# encore_Control_Board.net
KiCad netlist of a schematic drawn in EAGLE
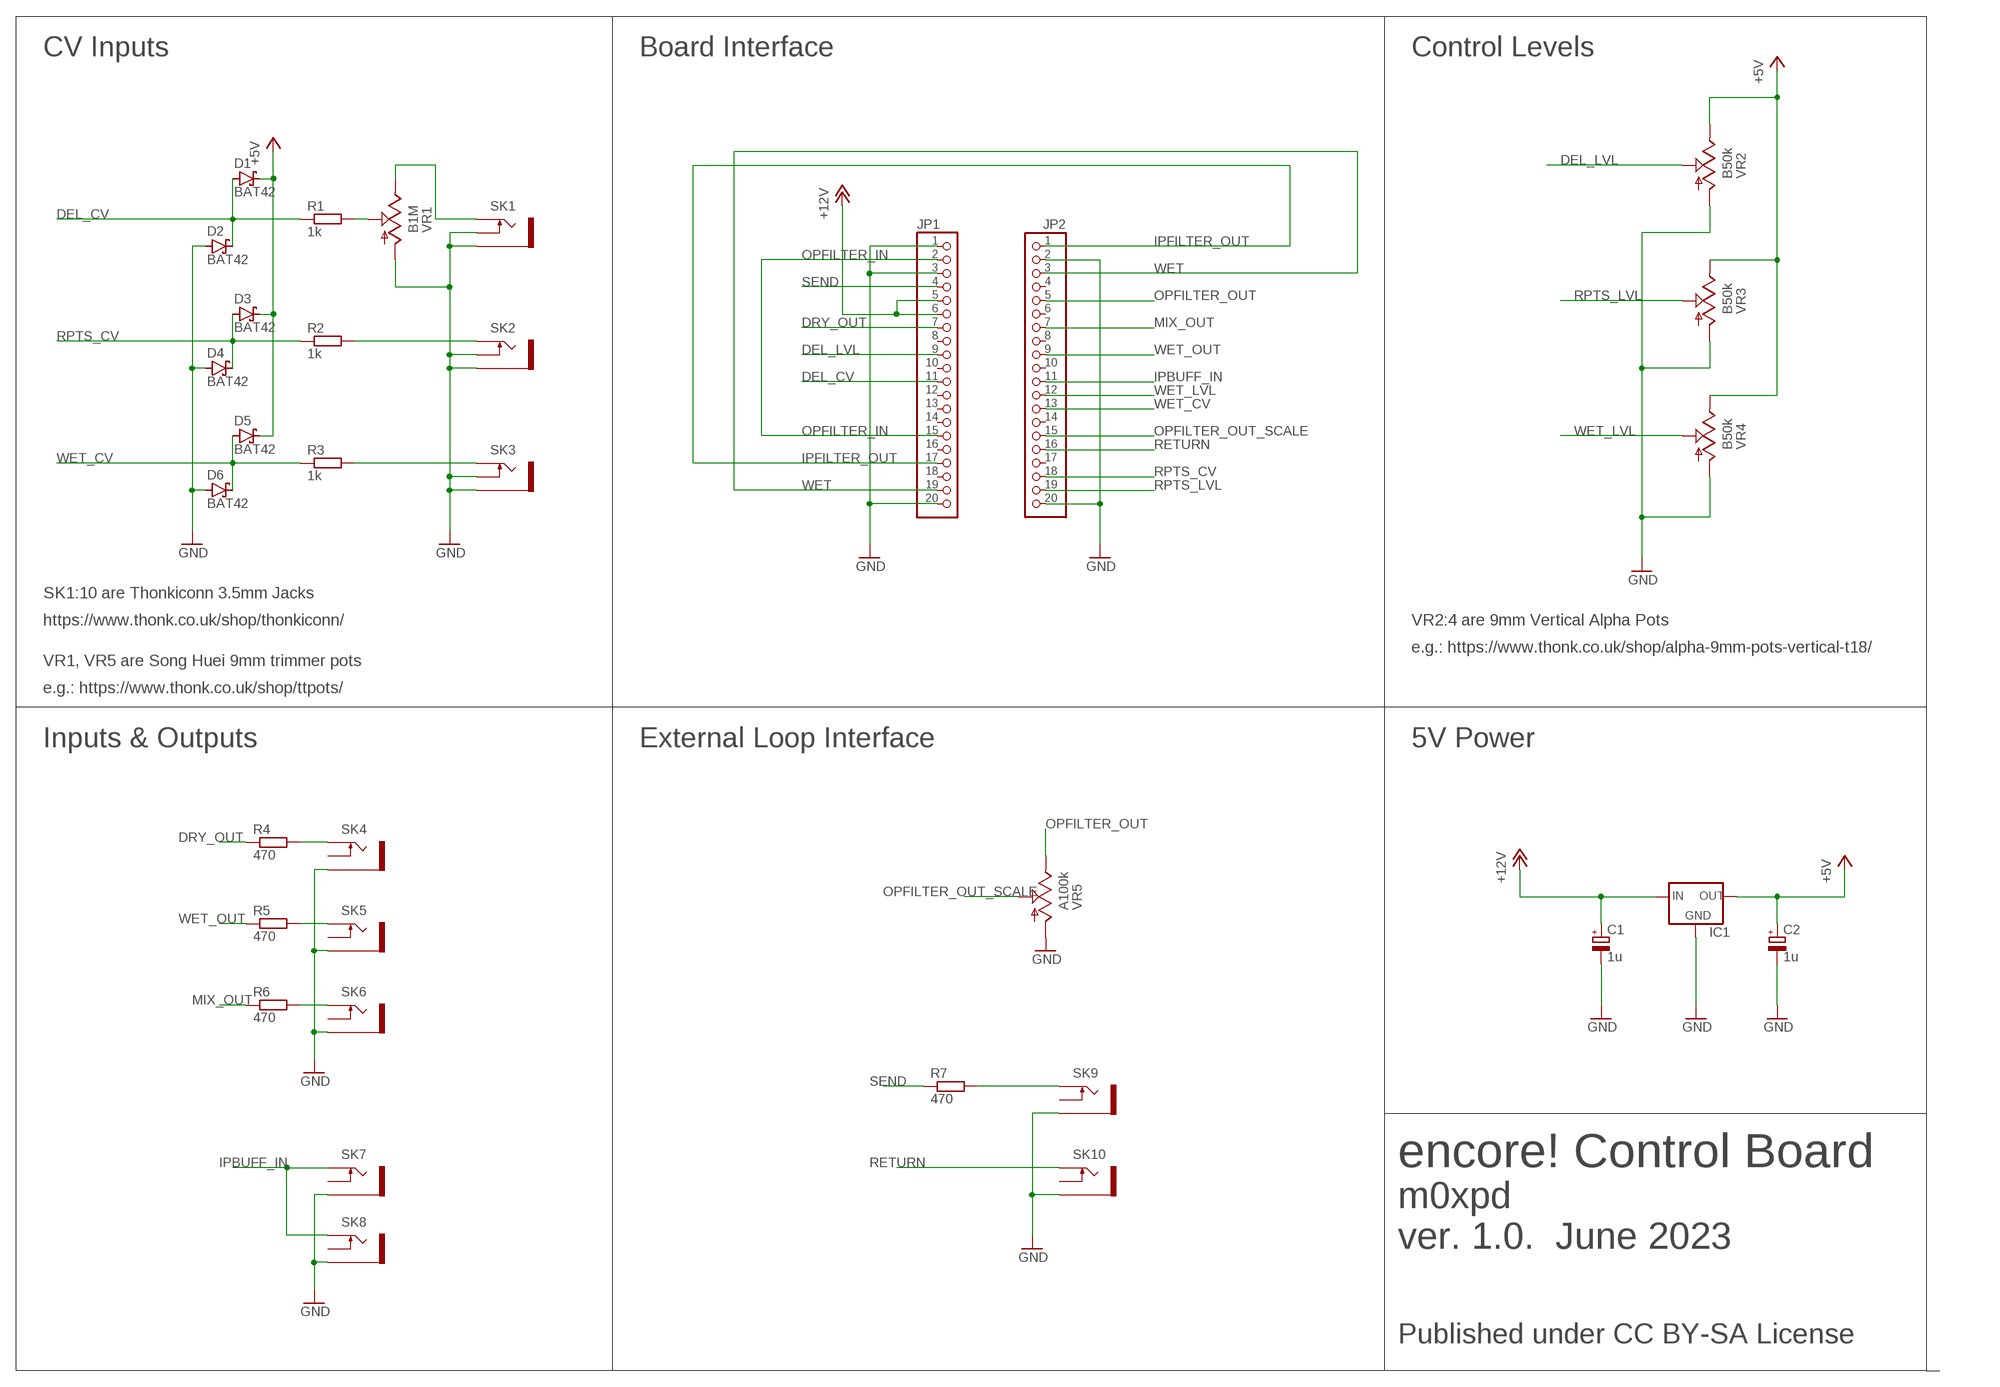
[diagram p0: schematic, sheet 1]

(export (version "E")
  (design (tool "Eeschema 10.0.6"))
  (components
    (comp (ref "C1")
      (value "1u")
      (footprint "eagle-import:E2,5-5")
      (libsource (lib "eagle-import") (part "CPOL-EUE2.5-5"))
    )
    (comp (ref "C2")
      (value "1u")
      (footprint "eagle-import:E2,5-5")
      (libsource (lib "eagle-import") (part "CPOL-EUE2.5-5"))
    )
    (comp (ref "D1")
      (value "BAT42")
      (footprint "eagle-import:DO35-10")
      (libsource (lib "eagle-import") (part "BAT42"))
    )
    (comp (ref "D2")
      (value "BAT42")
      (footprint "eagle-import:DO35-10")
      (libsource (lib "eagle-import") (part "BAT42"))
    )
    (comp (ref "D3")
      (value "BAT42")
      (footprint "eagle-import:DO35-10")
      (libsource (lib "eagle-import") (part "BAT42"))
    )
    (comp (ref "D4")
      (value "BAT42")
      (footprint "eagle-import:DO35-10")
      (libsource (lib "eagle-import") (part "BAT42"))
    )
    (comp (ref "D5")
      (value "BAT42")
      (footprint "eagle-import:DO35-10")
      (libsource (lib "eagle-import") (part "BAT42"))
    )
    (comp (ref "D6")
      (value "BAT42")
      (footprint "eagle-import:DO35-10")
      (libsource (lib "eagle-import") (part "BAT42"))
    )
    (comp (ref "IC1")
      (value "78LXX")
      (footprint "eagle-import:78LXX")
      (libsource (lib "eagle-import") (part "78LXX"))
    )
    (comp (ref "JP1")
      (value "PINHD-1X20")
      (footprint "eagle-import:1X20")
      (libsource (lib "eagle-import") (part "PINHD-1X20"))
    )
    (comp (ref "JP2")
      (value "PINHD-1X20")
      (footprint "eagle-import:1X20")
      (libsource (lib "eagle-import") (part "PINHD-1X20"))
    )
    (comp (ref "R1")
      (value "1k")
      (footprint "eagle-import:0204_7")
      (libsource (lib "eagle-import") (part "R-EU_0204/7"))
    )
    (comp (ref "R2")
      (value "1k")
      (footprint "eagle-import:0204_7")
      (libsource (lib "eagle-import") (part "R-EU_0204/7"))
    )
    (comp (ref "R3")
      (value "1k")
      (footprint "eagle-import:0204_7")
      (libsource (lib "eagle-import") (part "R-EU_0204/7"))
    )
    (comp (ref "R4")
      (value "470")
      (footprint "eagle-import:0204_7")
      (libsource (lib "eagle-import") (part "R-EU_0204/7"))
    )
    (comp (ref "R5")
      (value "470")
      (footprint "eagle-import:0204_7")
      (libsource (lib "eagle-import") (part "R-EU_0204/7"))
    )
    (comp (ref "R6")
      (value "470")
      (footprint "eagle-import:0204_7")
      (libsource (lib "eagle-import") (part "R-EU_0204/7"))
    )
    (comp (ref "R7")
      (value "470")
      (footprint "eagle-import:0204_7")
      (libsource (lib "eagle-import") (part "R-EU_0204/7"))
    )
    (comp (ref "SK1")
      (value "THONKICONN_JACK")
      (footprint "eagle-import:WQP-PJ301M-12_JACK")
      (libsource (lib "eagle-import") (part "THONKICONN_JACK"))
    )
    (comp (ref "SK2")
      (value "THONKICONN_JACK")
      (footprint "eagle-import:WQP-PJ301M-12_JACK")
      (libsource (lib "eagle-import") (part "THONKICONN_JACK"))
    )
    (comp (ref "SK3")
      (value "THONKICONN_JACK")
      (footprint "eagle-import:WQP-PJ301M-12_JACK")
      (libsource (lib "eagle-import") (part "THONKICONN_JACK"))
    )
    (comp (ref "SK4")
      (value "THONKICONN_JACK")
      (footprint "eagle-import:WQP-PJ301M-12_JACK")
      (libsource (lib "eagle-import") (part "THONKICONN_JACK"))
    )
    (comp (ref "SK5")
      (value "THONKICONN_JACK")
      (footprint "eagle-import:WQP-PJ301M-12_JACK")
      (libsource (lib "eagle-import") (part "THONKICONN_JACK"))
    )
    (comp (ref "SK6")
      (value "THONKICONN_JACK")
      (footprint "eagle-import:WQP-PJ301M-12_JACK")
      (libsource (lib "eagle-import") (part "THONKICONN_JACK"))
    )
    (comp (ref "SK7")
      (value "THONKICONN_JACK")
      (footprint "eagle-import:WQP-PJ301M-12_JACK")
      (libsource (lib "eagle-import") (part "THONKICONN_JACK"))
    )
    (comp (ref "SK8")
      (value "THONKICONN_JACK")
      (footprint "eagle-import:WQP-PJ301M-12_JACK")
      (libsource (lib "eagle-import") (part "THONKICONN_JACK"))
    )
    (comp (ref "SK9")
      (value "THONKICONN_JACK")
      (footprint "eagle-import:WQP-PJ301M-12_JACK")
      (libsource (lib "eagle-import") (part "THONKICONN_JACK"))
    )
    (comp (ref "SK10")
      (value "THONKICONN_JACK")
      (footprint "eagle-import:WQP-PJ301M-12_JACK")
      (libsource (lib "eagle-import") (part "THONKICONN_JACK"))
    )
    (comp (ref "VR1")
      (value "B1M")
      (footprint "eagle-import:9MM_SNAP-IN_POT")
      (libsource (lib "eagle-import") (part "9MM_SNAP-IN_POT_"))
    )
    (comp (ref "VR2")
      (value "B50k")
      (footprint "eagle-import:9MM_SNAP-IN_POT")
      (libsource (lib "eagle-import") (part "9MM_SNAP-IN_POT_"))
    )
    (comp (ref "VR3")
      (value "B50k")
      (footprint "eagle-import:9MM_SNAP-IN_POT")
      (libsource (lib "eagle-import") (part "9MM_SNAP-IN_POT_"))
    )
    (comp (ref "VR4")
      (value "B50k")
      (footprint "eagle-import:9MM_SNAP-IN_POT")
      (libsource (lib "eagle-import") (part "9MM_SNAP-IN_POT_"))
    )
    (comp (ref "VR5")
      (value "A100k")
      (footprint "eagle-import:9MM_SNAP-IN_POT")
      (libsource (lib "eagle-import") (part "9MM_SNAP-IN_POT_"))
    )
  )
  (nets
    (net (code "1") (name "+5V") (class "Default")
      (node (ref "C2") (pin "+") (pinfunction "+_+") (pintype "passive"))
      (node (ref "D1") (pin "C") (pinfunction "C_C") (pintype "passive"))
      (node (ref "D3") (pin "C") (pinfunction "C_C") (pintype "passive"))
      (node (ref "D5") (pin "C") (pinfunction "C_C") (pintype "passive"))
      (node (ref "IC1") (pin "OUT") (pinfunction "OUT_OUT") (pintype "passive"))
      (node (ref "VR2") (pin "3") (pinfunction "E_3") (pintype "passive"))
      (node (ref "VR3") (pin "3") (pinfunction "E_3") (pintype "passive"))
      (node (ref "VR4") (pin "3") (pinfunction "E_3") (pintype "passive"))
    )
    (net (code "2") (name "+12V") (class "Default")
      (node (ref "C1") (pin "+") (pinfunction "+_+") (pintype "passive"))
      (node (ref "IC1") (pin "IN") (pinfunction "IN_IN") (pintype "input"))
      (node (ref "JP1") (pin "5") (pinfunction "5_5") (pintype "passive"))
      (node (ref "JP1") (pin "6") (pinfunction "6_6") (pintype "passive"))
    )
    (net (code "3") (name "/DEL_CV") (class "Default")
      (node (ref "D1") (pin "A") (pinfunction "A_A") (pintype "passive"))
      (node (ref "D2") (pin "C") (pinfunction "C_C") (pintype "passive"))
      (node (ref "JP1") (pin "11") (pinfunction "11_11") (pintype "passive"))
      (node (ref "R1") (pin "1") (pinfunction "1_1") (pintype "passive"))
    )
    (net (code "4") (name "/DEL_LVL") (class "Default")
      (node (ref "JP1") (pin "9") (pinfunction "9_9") (pintype "passive"))
      (node (ref "VR2") (pin "2") (pinfunction "S_2") (pintype "passive"))
    )
    (net (code "5") (name "/DRY_OUT") (class "Default")
      (node (ref "JP1") (pin "7") (pinfunction "7_7") (pintype "passive"))
      (node (ref "R4") (pin "1") (pinfunction "1_1") (pintype "passive"))
    )
    (net (code "6") (name "/IPBUFF_IN") (class "Default")
      (node (ref "JP2") (pin "11") (pinfunction "11_11") (pintype "passive"))
      (node (ref "SK7") (pin "P$1_TIP") (pinfunction "TIP_P$1_TIP") (pintype "passive"))
      (node (ref "SK8") (pin "P$1_TIP") (pinfunction "TIP_P$1_TIP") (pintype "passive"))
    )
    (net (code "7") (name "/IPFILTER_OUT") (class "Default")
      (node (ref "JP1") (pin "17") (pinfunction "17_17") (pintype "passive"))
      (node (ref "JP2") (pin "1") (pinfunction "1_1") (pintype "passive"))
    )
    (net (code "8") (name "/MIX_OUT") (class "Default")
      (node (ref "JP2") (pin "7") (pinfunction "7_7") (pintype "passive"))
      (node (ref "R6") (pin "1") (pinfunction "1_1") (pintype "passive"))
    )
    (net (code "9") (name "/OPFILTER_IN") (class "Default")
      (node (ref "JP1") (pin "15") (pinfunction "15_15") (pintype "passive"))
      (node (ref "JP1") (pin "2") (pinfunction "2_2") (pintype "passive"))
    )
    (net (code "10") (name "/OPFILTER_OUT") (class "Default")
      (node (ref "JP2") (pin "5") (pinfunction "5_5") (pintype "passive"))
      (node (ref "VR5") (pin "3") (pinfunction "E_3") (pintype "passive"))
    )
    (net (code "11") (name "/OPFILTER_OUT_SCALE") (class "Default")
      (node (ref "JP2") (pin "15") (pinfunction "15_15") (pintype "passive"))
      (node (ref "VR5") (pin "2") (pinfunction "S_2") (pintype "passive"))
    )
    (net (code "12") (name "/RETURN") (class "Default")
      (node (ref "JP2") (pin "16") (pinfunction "16_16") (pintype "passive"))
      (node (ref "SK10") (pin "P$1_TIP") (pinfunction "TIP_P$1_TIP") (pintype "passive"))
    )
    (net (code "13") (name "/RPTS_CV") (class "Default")
      (node (ref "D3") (pin "A") (pinfunction "A_A") (pintype "passive"))
      (node (ref "D4") (pin "C") (pinfunction "C_C") (pintype "passive"))
      (node (ref "JP2") (pin "18") (pinfunction "18_18") (pintype "passive"))
      (node (ref "R2") (pin "1") (pinfunction "1_1") (pintype "passive"))
    )
    (net (code "14") (name "/RPTS_LVL") (class "Default")
      (node (ref "JP2") (pin "19") (pinfunction "19_19") (pintype "passive"))
      (node (ref "VR3") (pin "2") (pinfunction "S_2") (pintype "passive"))
    )
    (net (code "15") (name "/SEND") (class "Default")
      (node (ref "JP1") (pin "4") (pinfunction "4_4") (pintype "passive"))
      (node (ref "R7") (pin "1") (pinfunction "1_1") (pintype "passive"))
    )
    (net (code "16") (name "/WET") (class "Default")
      (node (ref "JP1") (pin "19") (pinfunction "19_19") (pintype "passive"))
      (node (ref "JP2") (pin "3") (pinfunction "3_3") (pintype "passive"))
    )
    (net (code "17") (name "/WET_CV") (class "Default")
      (node (ref "D5") (pin "A") (pinfunction "A_A") (pintype "passive"))
      (node (ref "D6") (pin "C") (pinfunction "C_C") (pintype "passive"))
      (node (ref "JP2") (pin "13") (pinfunction "13_13") (pintype "passive"))
      (node (ref "R3") (pin "1") (pinfunction "1_1") (pintype "passive"))
    )
    (net (code "18") (name "/WET_LVL") (class "Default")
      (node (ref "JP2") (pin "12") (pinfunction "12_12") (pintype "passive"))
      (node (ref "VR4") (pin "2") (pinfunction "S_2") (pintype "passive"))
    )
    (net (code "19") (name "/WET_OUT") (class "Default")
      (node (ref "JP2") (pin "9") (pinfunction "9_9") (pintype "passive"))
      (node (ref "R5") (pin "1") (pinfunction "1_1") (pintype "passive"))
    )
    (net (code "20") (name "GND") (class "Default")
      (node (ref "C1") (pin "-") (pinfunction "-_-") (pintype "passive"))
      (node (ref "C2") (pin "-") (pinfunction "-_-") (pintype "passive"))
      (node (ref "D2") (pin "A") (pinfunction "A_A") (pintype "passive"))
      (node (ref "D4") (pin "A") (pinfunction "A_A") (pintype "passive"))
      (node (ref "D6") (pin "A") (pinfunction "A_A") (pintype "passive"))
      (node (ref "IC1") (pin "GND") (pinfunction "GND_GND") (pintype "input"))
      (node (ref "JP1") (pin "1") (pinfunction "1_1") (pintype "passive"))
      (node (ref "JP1") (pin "20") (pinfunction "20_20") (pintype "passive"))
      (node (ref "JP1") (pin "3") (pinfunction "3_3") (pintype "passive"))
      (node (ref "JP2") (pin "2") (pinfunction "2_2") (pintype "passive"))
      (node (ref "JP2") (pin "20") (pinfunction "20_20") (pintype "passive"))
      (node (ref "SK1") (pin "P$2_SWITCH") (pinfunction "SWITCH_P$2_SWITCH") (pintype "passive"))
      (node (ref "SK1") (pin "P$3_SLEEVE") (pinfunction "SLEEVE_P$3_SLEEVE") (pintype "passive"))
      (node (ref "SK10") (pin "P$3_SLEEVE") (pinfunction "SLEEVE_P$3_SLEEVE") (pintype "passive"))
      (node (ref "SK2") (pin "P$2_SWITCH") (pinfunction "SWITCH_P$2_SWITCH") (pintype "passive"))
      (node (ref "SK2") (pin "P$3_SLEEVE") (pinfunction "SLEEVE_P$3_SLEEVE") (pintype "passive"))
      (node (ref "SK3") (pin "P$2_SWITCH") (pinfunction "SWITCH_P$2_SWITCH") (pintype "passive"))
      (node (ref "SK3") (pin "P$3_SLEEVE") (pinfunction "SLEEVE_P$3_SLEEVE") (pintype "passive"))
      (node (ref "SK4") (pin "P$3_SLEEVE") (pinfunction "SLEEVE_P$3_SLEEVE") (pintype "passive"))
      (node (ref "SK5") (pin "P$3_SLEEVE") (pinfunction "SLEEVE_P$3_SLEEVE") (pintype "passive"))
      (node (ref "SK6") (pin "P$3_SLEEVE") (pinfunction "SLEEVE_P$3_SLEEVE") (pintype "passive"))
      (node (ref "SK7") (pin "P$3_SLEEVE") (pinfunction "SLEEVE_P$3_SLEEVE") (pintype "passive"))
      (node (ref "SK8") (pin "P$3_SLEEVE") (pinfunction "SLEEVE_P$3_SLEEVE") (pintype "passive"))
      (node (ref "SK9") (pin "P$3_SLEEVE") (pinfunction "SLEEVE_P$3_SLEEVE") (pintype "passive"))
      (node (ref "VR1") (pin "1") (pinfunction "A_1") (pintype "passive"))
      (node (ref "VR2") (pin "1") (pinfunction "A_1") (pintype "passive"))
      (node (ref "VR3") (pin "1") (pinfunction "A_1") (pintype "passive"))
      (node (ref "VR4") (pin "1") (pinfunction "A_1") (pintype "passive"))
      (node (ref "VR5") (pin "1") (pinfunction "A_1") (pintype "passive"))
    )
    (net (code "21") (name "Net-(SK1-TIP)") (class "Default")
      (node (ref "SK1") (pin "P$1_TIP") (pinfunction "TIP_P$1_TIP") (pintype "passive"))
      (node (ref "VR1") (pin "3") (pinfunction "E_3") (pintype "passive"))
    )
    (net (code "22") (name "Net-(SK2-TIP)") (class "Default")
      (node (ref "R2") (pin "2") (pinfunction "2_2") (pintype "passive"))
      (node (ref "SK2") (pin "P$1_TIP") (pinfunction "TIP_P$1_TIP") (pintype "passive"))
    )
    (net (code "23") (name "Net-(SK3-TIP)") (class "Default")
      (node (ref "R3") (pin "2") (pinfunction "2_2") (pintype "passive"))
      (node (ref "SK3") (pin "P$1_TIP") (pinfunction "TIP_P$1_TIP") (pintype "passive"))
    )
    (net (code "24") (name "Net-(SK4-TIP)") (class "Default")
      (node (ref "R4") (pin "2") (pinfunction "2_2") (pintype "passive"))
      (node (ref "SK4") (pin "P$1_TIP") (pinfunction "TIP_P$1_TIP") (pintype "passive"))
    )
    (net (code "25") (name "Net-(SK5-TIP)") (class "Default")
      (node (ref "R5") (pin "2") (pinfunction "2_2") (pintype "passive"))
      (node (ref "SK5") (pin "P$1_TIP") (pinfunction "TIP_P$1_TIP") (pintype "passive"))
    )
    (net (code "26") (name "Net-(SK6-TIP)") (class "Default")
      (node (ref "R6") (pin "2") (pinfunction "2_2") (pintype "passive"))
      (node (ref "SK6") (pin "P$1_TIP") (pinfunction "TIP_P$1_TIP") (pintype "passive"))
    )
    (net (code "27") (name "Net-(SK9-TIP)") (class "Default")
      (node (ref "R7") (pin "2") (pinfunction "2_2") (pintype "passive"))
      (node (ref "SK9") (pin "P$1_TIP") (pinfunction "TIP_P$1_TIP") (pintype "passive"))
    )
    (net (code "28") (name "Net-(VR1-S)") (class "Default")
      (node (ref "R1") (pin "2") (pinfunction "2_2") (pintype "passive"))
      (node (ref "VR1") (pin "2") (pinfunction "S_2") (pintype "passive"))
    )
    (net (code "29") (name "unconnected-(JP1-Pad8)") (class "Default")
      (node (ref "JP1") (pin "8") (pinfunction "8_8") (pintype "passive"))
    )
    (net (code "30") (name "unconnected-(JP1-Pad10)") (class "Default")
      (node (ref "JP1") (pin "10") (pinfunction "10_10") (pintype "passive"))
    )
    (net (code "31") (name "unconnected-(JP1-Pad12)") (class "Default")
      (node (ref "JP1") (pin "12") (pinfunction "12_12") (pintype "passive"))
    )
    (net (code "32") (name "unconnected-(JP1-Pad13)") (class "Default")
      (node (ref "JP1") (pin "13") (pinfunction "13_13") (pintype "passive"))
    )
    (net (code "33") (name "unconnected-(JP1-Pad14)") (class "Default")
      (node (ref "JP1") (pin "14") (pinfunction "14_14") (pintype "passive"))
    )
    (net (code "34") (name "unconnected-(JP1-Pad16)") (class "Default")
      (node (ref "JP1") (pin "16") (pinfunction "16_16") (pintype "passive"))
    )
    (net (code "35") (name "unconnected-(JP1-Pad18)") (class "Default")
      (node (ref "JP1") (pin "18") (pinfunction "18_18") (pintype "passive"))
    )
    (net (code "36") (name "unconnected-(JP2-Pad4)") (class "Default")
      (node (ref "JP2") (pin "4") (pinfunction "4_4") (pintype "passive"))
    )
    (net (code "37") (name "unconnected-(JP2-Pad6)") (class "Default")
      (node (ref "JP2") (pin "6") (pinfunction "6_6") (pintype "passive"))
    )
    (net (code "38") (name "unconnected-(JP2-Pad8)") (class "Default")
      (node (ref "JP2") (pin "8") (pinfunction "8_8") (pintype "passive"))
    )
    (net (code "39") (name "unconnected-(JP2-Pad10)") (class "Default")
      (node (ref "JP2") (pin "10") (pinfunction "10_10") (pintype "passive"))
    )
    (net (code "40") (name "unconnected-(JP2-Pad14)") (class "Default")
      (node (ref "JP2") (pin "14") (pinfunction "14_14") (pintype "passive"))
    )
    (net (code "41") (name "unconnected-(JP2-Pad17)") (class "Default")
      (node (ref "JP2") (pin "17") (pinfunction "17_17") (pintype "passive"))
    )
    (net (code "42") (name "unconnected-(SK4-SWITCH-PadP$2_SWITCH)") (class "Default")
      (node (ref "SK4") (pin "P$2_SWITCH") (pinfunction "SWITCH_P$2_SWITCH") (pintype "passive"))
    )
    (net (code "43") (name "unconnected-(SK5-SWITCH-PadP$2_SWITCH)") (class "Default")
      (node (ref "SK5") (pin "P$2_SWITCH") (pinfunction "SWITCH_P$2_SWITCH") (pintype "passive"))
    )
    (net (code "44") (name "unconnected-(SK6-SWITCH-PadP$2_SWITCH)") (class "Default")
      (node (ref "SK6") (pin "P$2_SWITCH") (pinfunction "SWITCH_P$2_SWITCH") (pintype "passive"))
    )
    (net (code "45") (name "unconnected-(SK7-SWITCH-PadP$2_SWITCH)") (class "Default")
      (node (ref "SK7") (pin "P$2_SWITCH") (pinfunction "SWITCH_P$2_SWITCH") (pintype "passive"))
    )
    (net (code "46") (name "unconnected-(SK8-SWITCH-PadP$2_SWITCH)") (class "Default")
      (node (ref "SK8") (pin "P$2_SWITCH") (pinfunction "SWITCH_P$2_SWITCH") (pintype "passive"))
    )
    (net (code "47") (name "unconnected-(SK9-SWITCH-PadP$2_SWITCH)") (class "Default")
      (node (ref "SK9") (pin "P$2_SWITCH") (pinfunction "SWITCH_P$2_SWITCH") (pintype "passive"))
    )
    (net (code "48") (name "unconnected-(SK10-SWITCH-PadP$2_SWITCH)") (class "Default")
      (node (ref "SK10") (pin "P$2_SWITCH") (pinfunction "SWITCH_P$2_SWITCH") (pintype "passive"))
    )
  )
)
